# Proiect_TSC_2025.net
KiCad netlist of a schematic drawn in EAGLE
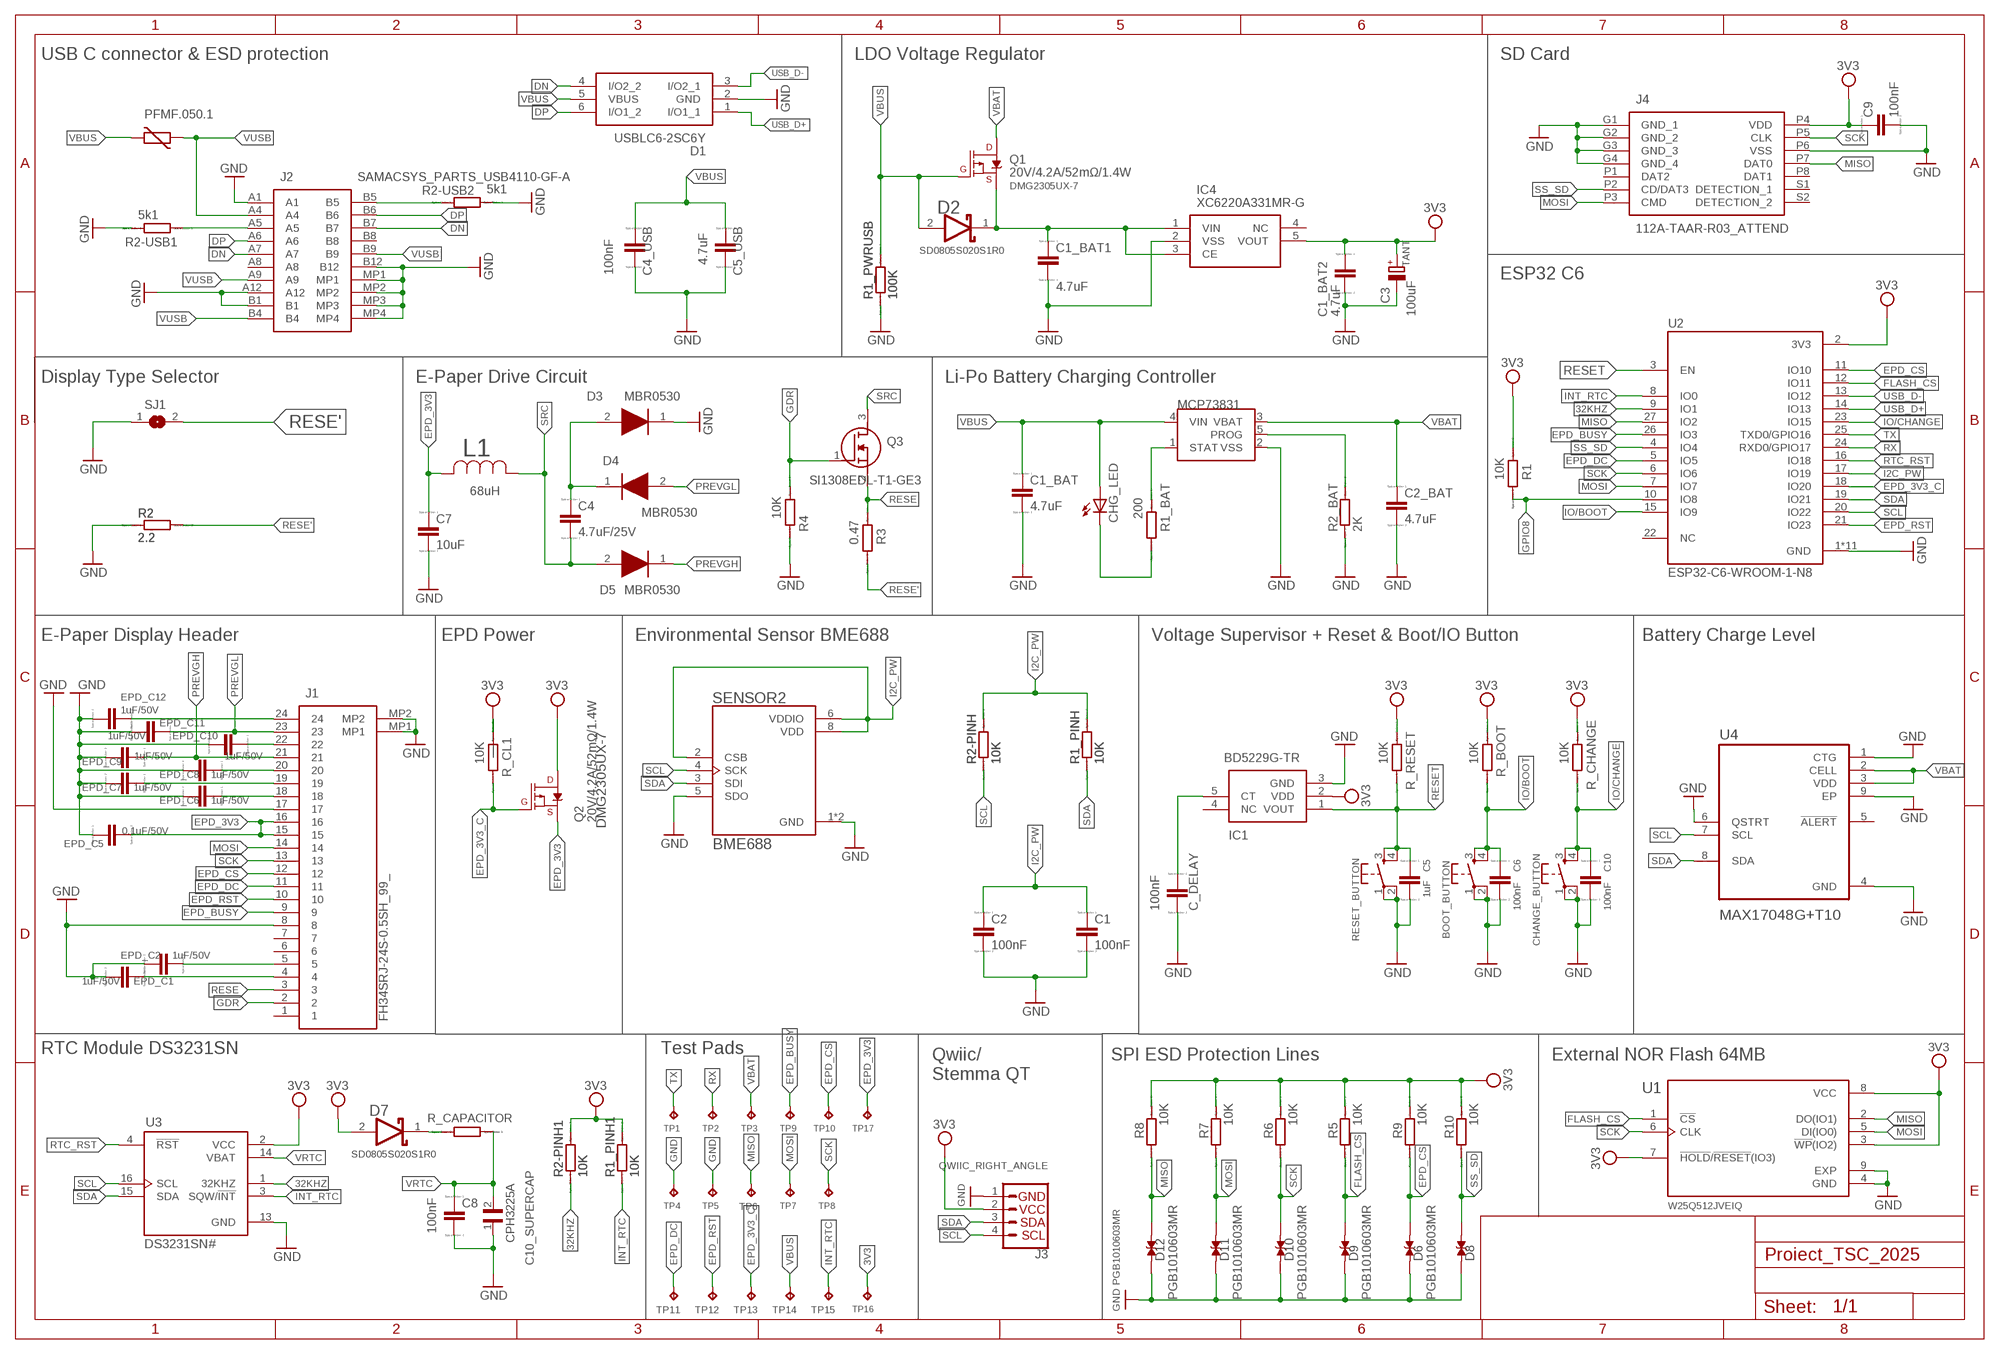
[diagram p0: schematic, sheet 1]

(export (version "E")
  (design (tool "Eeschema 10.0.6"))
  (components
    (comp (ref "BOOT_BUTTON")
      (value "BUTTON_CUSYOMV1")
      (footprint "eagle-import:MYBUTTON")
      (libsource (lib "eagle-import") (part "BUTTON_CUSYOMV1"))
    )
    (comp (ref "C1")
      (value "100nF")
      (footprint "eagle-import:ESP32_WROVER_EAGLE-LTSPICE_C0402")
      (libsource (lib "eagle-import") (part "ESP32_WROVER_EAGLE-LTSPICE_CC0402"))
    )
    (comp (ref "C1_BAT")
      (value "4.7uF")
      (footprint "eagle-import:ESP32_WROVER_EAGLE-LTSPICE_C0402")
      (libsource (lib "eagle-import") (part "ESP32_WROVER_EAGLE-LTSPICE_CC0402"))
    )
    (comp (ref "C1_BAT1")
      (value "4.7uF")
      (footprint "eagle-import:ESP32_WROVER_EAGLE-LTSPICE_C0402")
      (libsource (lib "eagle-import") (part "ESP32_WROVER_EAGLE-LTSPICE_CC0402"))
    )
    (comp (ref "C1_BAT2")
      (value "4.7uF")
      (footprint "eagle-import:ESP32_WROVER_EAGLE-LTSPICE_C0402")
      (libsource (lib "eagle-import") (part "ESP32_WROVER_EAGLE-LTSPICE_CC0402"))
    )
    (comp (ref "C2")
      (value "100nF")
      (footprint "eagle-import:ESP32_WROVER_EAGLE-LTSPICE_C0402")
      (libsource (lib "eagle-import") (part "ESP32_WROVER_EAGLE-LTSPICE_CC0402"))
    )
    (comp (ref "C2_BAT")
      (value "4.7uF")
      (footprint "eagle-import:ESP32_WROVER_EAGLE-LTSPICE_C0402")
      (libsource (lib "eagle-import") (part "ESP32_WROVER_EAGLE-LTSPICE_CC0402"))
    )
    (comp (ref "C3")
      (value "100uF")
      (footprint "eagle-import:RCL_CT3528")
      (libsource (lib "eagle-import") (part "RCL_CPOL-EUCT3528"))
    )
    (comp (ref "C4")
      (value "4.7uF/25V")
      (footprint "eagle-import:ESP32_WROVER_EAGLE-LTSPICE_C0402")
      (libsource (lib "eagle-import") (part "ESP32_WROVER_EAGLE-LTSPICE_CC0402"))
    )
    (comp (ref "C4_USB")
      (value "100nF")
      (footprint "eagle-import:EAGLE-LTSPICE_C0402")
      (libsource (lib "eagle-import") (part "EAGLE-LTSPICE_CC0402"))
    )
    (comp (ref "C5")
      (value "1uF")
      (footprint "eagle-import:ESP32_WROVER_EAGLE-LTSPICE_C0402")
      (libsource (lib "eagle-import") (part "ESP32_WROVER_EAGLE-LTSPICE_CC0402"))
    )
    (comp (ref "C5_USB")
      (value "4.7uF")
      (footprint "eagle-import:EAGLE-LTSPICE_C0402")
      (libsource (lib "eagle-import") (part "EAGLE-LTSPICE_CC0402"))
    )
    (comp (ref "C6")
      (value "100nF")
      (footprint "eagle-import:ESP32_WROVER_EAGLE-LTSPICE_C0402")
      (libsource (lib "eagle-import") (part "ESP32_WROVER_EAGLE-LTSPICE_CC0402"))
    )
    (comp (ref "C7")
      (value "10uF")
      (footprint "eagle-import:ESP32_WROVER_EAGLE-LTSPICE_C0402")
      (libsource (lib "eagle-import") (part "ESP32_WROVER_EAGLE-LTSPICE_CC0402"))
    )
    (comp (ref "C8")
      (value "100nF")
      (footprint "eagle-import:ESP32_WROVER_EAGLE-LTSPICE_C0402")
      (libsource (lib "eagle-import") (part "ESP32_WROVER_EAGLE-LTSPICE_CC0402"))
    )
    (comp (ref "C9")
      (value "100nF")
      (footprint "eagle-import:ESP32_WROVER_EAGLE-LTSPICE_C0402")
      (libsource (lib "eagle-import") (part "ESP32_WROVER_EAGLE-LTSPICE_CC0402"))
    )
    (comp (ref "C10")
      (value "100nF")
      (footprint "eagle-import:ESP32_WROVER_EAGLE-LTSPICE_C0402")
      (libsource (lib "eagle-import") (part "ESP32_WROVER_EAGLE-LTSPICE_CC0402"))
    )
    (comp (ref "C10_SUPERCAP")
      (value "CPH3225A")
      (footprint "eagle-import:CAPCP3225X100N")
      (fields (field (name "MF") "Seiko Instruments"))
      (libsource (lib "eagle-import") (part "CPH3225A"))
    )
    (comp (ref "CHANGE_BUTTON")
      (value "CHANGE_BUTTON")
      (footprint "eagle-import:MYBUTTON")
      (libsource (lib "eagle-import") (part "BUTTON_CUSYOMV1"))
    )
    (comp (ref "CHG_LED")
      (value "ADAFRUIT_LEDCHIP-LED0603")
      (footprint "eagle-import:ADAFRUIT_CHIP-LED0603")
      (libsource (lib "eagle-import") (part "ADAFRUIT_LEDCHIP-LED0603"))
    )
    (comp (ref "C_DELAY")
      (value "100nF")
      (footprint "eagle-import:ESP32_WROVER_EAGLE-LTSPICE_C0402")
      (libsource (lib "eagle-import") (part "ESP32_WROVER_EAGLE-LTSPICE_CC0402"))
    )
    (comp (ref "D1")
      (value "USBLC6-2SC6Y")
      (footprint "eagle-import:SOT95P280X145-6N")
      (fields (field (name "MF") "STMicroelectronics"))
      (libsource (lib "eagle-import") (part "USBLC6-2SC6Y"))
    )
    (comp (ref "D2")
      (value "ESP32_WROVER_AVX---SD0805S020S1R0_AVX_SD0805S020S1R0_0_0AVX_SD0805S020S1R0_0_0")
      (footprint "eagle-import:ESP32_WROVER_AVX---SD0805S020S1R0_AVX_SD0805S020S1R0_0")
      (fields
        (field (name "DIGIKEY_PART_NUMBER") "478-7800-1-ND")
        (field (name "MF") "AVX")
        (field (name "MOUSER_PART_NUMBER") "581-SD0805S020S1R0")
      )
      (libsource (lib "eagle-import") (part "ESP32_WROVER_AVX---SD0805S020S1R0_AVX_SD0805S020S1R0_0_0AVX_SD0805S020S1R0_0_0"))
    )
    (comp (ref "D3")
      (value "MBR0530")
      (footprint "eagle-import:SOD3716X135N")
      (fields (field (name "MF") "ON Semiconductor"))
      (libsource (lib "eagle-import") (part "MBR0530"))
    )
    (comp (ref "D4")
      (value "MBR0530")
      (footprint "eagle-import:SOD3716X135N")
      (fields (field (name "MF") "ON Semiconductor"))
      (libsource (lib "eagle-import") (part "MBR0530"))
    )
    (comp (ref "D5")
      (value "MBR0530")
      (footprint "eagle-import:SOD3716X135N")
      (fields (field (name "MF") "ON Semiconductor"))
      (libsource (lib "eagle-import") (part "MBR0530"))
    )
    (comp (ref "D6")
      (value "PGB1010603MR")
      (footprint "eagle-import:DIOC1608X36N")
      (fields (field (name "MF") "Littelfuse Inc."))
      (libsource (lib "eagle-import") (part "PGB1010603MR"))
    )
    (comp (ref "D7")
      (value "SD0805S020S1R0")
      (footprint "eagle-import:ESP32_WROVER_AVX---SD0805S020S1R0_AVX_SD0805S020S1R0_0")
      (fields
        (field (name "DIGIKEY_PART_NUMBER") "478-7800-1-ND")
        (field (name "MF") "AVX")
        (field (name "MOUSER_PART_NUMBER") "581-SD0805S020S1R0")
      )
      (libsource (lib "eagle-import") (part "ESP32_WROVER_AVX---SD0805S020S1R0_AVX_SD0805S020S1R0_0_0AVX_SD0805S020S1R0_0_0"))
    )
    (comp (ref "D8")
      (value "PGB1010603MR")
      (footprint "eagle-import:DIOC1608X36N")
      (fields (field (name "MF") "Littelfuse Inc."))
      (libsource (lib "eagle-import") (part "PGB1010603MR"))
    )
    (comp (ref "D9")
      (value "PGB1010603MR")
      (footprint "eagle-import:DIOC1608X36N")
      (fields (field (name "MF") "Littelfuse Inc."))
      (libsource (lib "eagle-import") (part "PGB1010603MR"))
    )
    (comp (ref "D10")
      (value "PGB1010603MR")
      (footprint "eagle-import:DIOC1608X36N")
      (fields (field (name "MF") "Littelfuse Inc."))
      (libsource (lib "eagle-import") (part "PGB1010603MR"))
    )
    (comp (ref "D11")
      (value "PGB1010603MR")
      (footprint "eagle-import:DIOC1608X36N")
      (fields (field (name "MF") "Littelfuse Inc."))
      (libsource (lib "eagle-import") (part "PGB1010603MR"))
    )
    (comp (ref "D12")
      (value "PGB1010603MR")
      (footprint "eagle-import:DIOC1608X36N")
      (fields (field (name "MF") "Littelfuse Inc."))
      (libsource (lib "eagle-import") (part "PGB1010603MR"))
    )
    (comp (ref "EPD_C1")
      (value "1uF/50V")
      (footprint "eagle-import:ESP32_WROVER_EAGLE-LTSPICE_C0402")
      (libsource (lib "eagle-import") (part "ESP32_WROVER_EAGLE-LTSPICE_CC0402"))
    )
    (comp (ref "EPD_C2")
      (value "1uF/50V")
      (footprint "eagle-import:ESP32_WROVER_EAGLE-LTSPICE_C0402")
      (libsource (lib "eagle-import") (part "ESP32_WROVER_EAGLE-LTSPICE_CC0402"))
    )
    (comp (ref "EPD_C5")
      (value "0.1uF/50V")
      (footprint "eagle-import:ESP32_WROVER_EAGLE-LTSPICE_C0402")
      (libsource (lib "eagle-import") (part "ESP32_WROVER_EAGLE-LTSPICE_CC0402"))
    )
    (comp (ref "EPD_C6")
      (value "1uF/50V")
      (footprint "eagle-import:ESP32_WROVER_EAGLE-LTSPICE_C0402")
      (libsource (lib "eagle-import") (part "ESP32_WROVER_EAGLE-LTSPICE_CC0402"))
    )
    (comp (ref "EPD_C7")
      (value "1uF/50V")
      (footprint "eagle-import:ESP32_WROVER_EAGLE-LTSPICE_C0402")
      (libsource (lib "eagle-import") (part "ESP32_WROVER_EAGLE-LTSPICE_CC0402"))
    )
    (comp (ref "EPD_C8")
      (value "1uF/50V")
      (footprint "eagle-import:ESP32_WROVER_EAGLE-LTSPICE_C0402")
      (libsource (lib "eagle-import") (part "ESP32_WROVER_EAGLE-LTSPICE_CC0402"))
    )
    (comp (ref "EPD_C9")
      (value "1uF/50V")
      (footprint "eagle-import:ESP32_WROVER_EAGLE-LTSPICE_C0402")
      (libsource (lib "eagle-import") (part "ESP32_WROVER_EAGLE-LTSPICE_CC0402"))
    )
    (comp (ref "EPD_C10")
      (value "1uF/50V")
      (footprint "eagle-import:ESP32_WROVER_EAGLE-LTSPICE_C0402")
      (libsource (lib "eagle-import") (part "ESP32_WROVER_EAGLE-LTSPICE_CC0402"))
    )
    (comp (ref "EPD_C11")
      (value "1uF/50V")
      (footprint "eagle-import:ESP32_WROVER_EAGLE-LTSPICE_C0402")
      (libsource (lib "eagle-import") (part "ESP32_WROVER_EAGLE-LTSPICE_CC0402"))
    )
    (comp (ref "EPD_C12")
      (value "1uF/50V")
      (footprint "eagle-import:ESP32_WROVER_EAGLE-LTSPICE_C0402")
      (libsource (lib "eagle-import") (part "ESP32_WROVER_EAGLE-LTSPICE_CC0402"))
    )
    (comp (ref "IC1")
      (value "BD5229G-TR")
      (footprint "eagle-import:SOT95P280X125-5N")
      (fields (field (name "MOUSER_PART_NUMBER") "755-BD5229G-TR"))
      (libsource (lib "eagle-import") (part "BD5229G-TR"))
    )
    (comp (ref "IC4")
      (value "XC6220A331MR-G")
      (footprint "eagle-import:SOT95P280X120-5N")
      (fields (field (name "MOUSER_PART_NUMBER") "865-XC6220A331MR-G"))
      (libsource (lib "eagle-import") (part "XC6220A331MR-G"))
    )
    (comp (ref "J1")
      (value "FH34SRJ-24S-0.5SH_99_")
      (footprint "eagle-import:FH34SRJ24S05SH99")
      (fields
        (field (name "MANUFACTURER_PART_NUMBER") "FH34SRJ-24S-0.5SH(99)")
        (field (name "MOUSER_PART_NUMBER") "798-FH34SRJ24S05SH99")
      )
      (libsource (lib "eagle-import") (part "FH34SRJ-24S-0.5SH_99_"))
    )
    (comp (ref "J2")
      (value "SAMACSYS_PARTS_USB4110-GF-A")
      (footprint "eagle-import:SAMACSYS_PARTS_USB4110GFA")
      (fields
        (field (name "MANUFACTURER_PART_NUMBER") "USB4110-GF-A")
        (field (name "MOUSER_PART_NUMBER") "640-USB4110-GF-A")
      )
      (libsource (lib "eagle-import") (part "SAMACSYS_PARTS_USB4110-GF-A"))
    )
    (comp (ref "J3")
      (value "QWIIC_RIGHT_ANGLE")
      (footprint "eagle-import:JST04_1MM_RA")
      (libsource (lib "eagle-import") (part "QWIIC_CONNECTORJS-1MM"))
    )
    (comp (ref "J4")
      (value "112A-TAAR-R03_ATTEND")
      (footprint "eagle-import:112ATAARR03ATTEND")
      (fields (field (name "MANUFACTURER_PART_NUMBER") "112A-TAAR-R03 ATTEND"))
      (libsource (lib "eagle-import") (part "112A-TAAR-R03_ATTEND"))
    )
    (comp (ref "L1")
      (value "68uH")
      (footprint "eagle-import:IND_4828-WE-TPC_WRE")
      (fields
        (field (name "MANUFACTURER_PART_NUMBER") "744043680")
        (field (name "COPYRIGHT") "Copyright (C) 2024 Ultra Librarian. All rights reserved.")
      )
      (libsource (lib "eagle-import") (part "744043680IND_4828-WE-TPC_WRE"))
    )
    (comp (ref "MCP73831")
      (value "MCP73831")
      (footprint "eagle-import:ESP32_WROVER_SPARKFUN-IC-POWER_SOT23-5")
      (libsource (lib "eagle-import") (part "ESP32_WROVER_SPARKFUN-IC-POWER_MCP73831"))
    )
    (comp (ref "PFMF.050.1")
      (value "ESP32C6_VARISTORCN1812")
      (footprint "eagle-import:ESP32C6_VARISTOR_CT_CN1812")
      (libsource (lib "eagle-import") (part "ESP32C6_VARISTORCN1812"))
    )
    (comp (ref "Q1")
      (value "20V/4.2A/52mΩ/1.4W")
      (footprint "eagle-import:ESP32_WROVER_SPARKFUN-DISCRETESEMI_SOT23-3")
      (libsource (lib "eagle-import") (part "ESP32_WROVER_SPARKFUN-DISCRETESEMI_MOSFET_PCH-DMG2305UX-7"))
    )
    (comp (ref "Q2")
      (value "20V/4.2A/52mΩ/1.4W")
      (footprint "eagle-import:ESP32_WROVER_SPARKFUN-DISCRETESEMI_SOT23-3")
      (libsource (lib "eagle-import") (part "ESP32_WROVER_SPARKFUN-DISCRETESEMI_MOSFET_PCH-DMG2305UX-7"))
    )
    (comp (ref "Q3")
      (value "SI1308EDL-T1-GE3")
      (footprint "eagle-import:SOT65P210X110-3N")
      (fields (field (name "MF") "Vishay Siliconix"))
      (libsource (lib "eagle-import") (part "SI1308EDL-T1-GE3"))
    )
    (comp (ref "R1")
      (value "10K")
      (footprint "eagle-import:ESP32_WROVER_EAGLE-LTSPICE_R0402")
      (libsource (lib "eagle-import") (part "ESP32_WROVER_EAGLE-LTSPICE_RR0402"))
    )
    (comp (ref "R1_BAT")
      (value "200")
      (footprint "eagle-import:ESP32_WROVER_EAGLE-LTSPICE_R0402")
      (libsource (lib "eagle-import") (part "ESP32_WROVER_EAGLE-LTSPICE_RR0402"))
    )
    (comp (ref "R1_PINH")
      (value "10K")
      (footprint "eagle-import:ESP32_WROVER_EAGLE-LTSPICE_R0402")
      (libsource (lib "eagle-import") (part "ESP32_WROVER_EAGLE-LTSPICE_RR0402"))
    )
    (comp (ref "R1_PINH1")
      (value "10K")
      (footprint "eagle-import:ESP32_WROVER_EAGLE-LTSPICE_R0402")
      (libsource (lib "eagle-import") (part "ESP32_WROVER_EAGLE-LTSPICE_RR0402"))
    )
    (comp (ref "R1_PWRUSB")
      (value "100K")
      (footprint "eagle-import:ESP32_WROVER_EAGLE-LTSPICE_R0402")
      (libsource (lib "eagle-import") (part "ESP32_WROVER_EAGLE-LTSPICE_RR0402"))
    )
    (comp (ref "R2")
      (value "2.2")
      (footprint "eagle-import:ESP32_WROVER_EAGLE-LTSPICE_R0402")
      (libsource (lib "eagle-import") (part "ESP32_WROVER_EAGLE-LTSPICE_RR0402"))
    )
    (comp (ref "R2-PINH")
      (value "10K")
      (footprint "eagle-import:ESP32_WROVER_EAGLE-LTSPICE_R0402")
      (libsource (lib "eagle-import") (part "ESP32_WROVER_EAGLE-LTSPICE_RR0402"))
    )
    (comp (ref "R2-PINH1")
      (value "10K")
      (footprint "eagle-import:ESP32_WROVER_EAGLE-LTSPICE_R0402")
      (libsource (lib "eagle-import") (part "ESP32_WROVER_EAGLE-LTSPICE_RR0402"))
    )
    (comp (ref "R2-USB1")
      (value "5k1")
      (footprint "eagle-import:ESP32_WROVER_EAGLE-LTSPICE_R0402")
      (libsource (lib "eagle-import") (part "ESP32_WROVER_EAGLE-LTSPICE_RR0402"))
    )
    (comp (ref "R2-USB2")
      (value "5k1")
      (footprint "eagle-import:ESP32_WROVER_EAGLE-LTSPICE_R0402")
      (libsource (lib "eagle-import") (part "ESP32_WROVER_EAGLE-LTSPICE_RR0402"))
    )
    (comp (ref "R2_BAT")
      (value "2K")
      (footprint "eagle-import:ESP32_WROVER_EAGLE-LTSPICE_R0402")
      (libsource (lib "eagle-import") (part "ESP32_WROVER_EAGLE-LTSPICE_RR0402"))
    )
    (comp (ref "R3")
      (value "0.47")
      (footprint "eagle-import:ESP32_WROVER_EAGLE-LTSPICE_R0402")
      (libsource (lib "eagle-import") (part "ESP32_WROVER_EAGLE-LTSPICE_RR0402"))
    )
    (comp (ref "R4")
      (value "10K")
      (footprint "eagle-import:ESP32_WROVER_EAGLE-LTSPICE_R0402")
      (libsource (lib "eagle-import") (part "ESP32_WROVER_EAGLE-LTSPICE_RR0402"))
    )
    (comp (ref "R5")
      (value "10K")
      (footprint "eagle-import:ESP32_WROVER_EAGLE-LTSPICE_R0402")
      (libsource (lib "eagle-import") (part "ESP32_WROVER_EAGLE-LTSPICE_RR0402"))
    )
    (comp (ref "R6")
      (value "10K")
      (footprint "eagle-import:ESP32_WROVER_EAGLE-LTSPICE_R0402")
      (libsource (lib "eagle-import") (part "ESP32_WROVER_EAGLE-LTSPICE_RR0402"))
    )
    (comp (ref "R7")
      (value "10K")
      (footprint "eagle-import:ESP32_WROVER_EAGLE-LTSPICE_R0402")
      (libsource (lib "eagle-import") (part "ESP32_WROVER_EAGLE-LTSPICE_RR0402"))
    )
    (comp (ref "R8")
      (value "10K")
      (footprint "eagle-import:ESP32_WROVER_EAGLE-LTSPICE_R0402")
      (libsource (lib "eagle-import") (part "ESP32_WROVER_EAGLE-LTSPICE_RR0402"))
    )
    (comp (ref "R9")
      (value "10K")
      (footprint "eagle-import:ESP32_WROVER_EAGLE-LTSPICE_R0402")
      (libsource (lib "eagle-import") (part "ESP32_WROVER_EAGLE-LTSPICE_RR0402"))
    )
    (comp (ref "R10")
      (value "10K")
      (footprint "eagle-import:ESP32_WROVER_EAGLE-LTSPICE_R0402")
      (libsource (lib "eagle-import") (part "ESP32_WROVER_EAGLE-LTSPICE_RR0402"))
    )
    (comp (ref "RESET_BUTTON")
      (value "BUTTON_CUSYOMV1")
      (footprint "eagle-import:MYBUTTON")
      (libsource (lib "eagle-import") (part "BUTTON_CUSYOMV1"))
    )
    (comp (ref "R_BOOT")
      (value "10K")
      (footprint "eagle-import:ESP32_WROVER_EAGLE-LTSPICE_R0402")
      (libsource (lib "eagle-import") (part "ESP32_WROVER_EAGLE-LTSPICE_RR0402"))
    )
    (comp (ref "R_CAPACITOR")
      (value "ESP32_WROVER_EAGLE-LTSPICE_RR0402")
      (footprint "eagle-import:ESP32_WROVER_EAGLE-LTSPICE_R0402")
      (libsource (lib "eagle-import") (part "ESP32_WROVER_EAGLE-LTSPICE_RR0402"))
    )
    (comp (ref "R_CHANGE")
      (value "10K")
      (footprint "eagle-import:ESP32_WROVER_EAGLE-LTSPICE_R0402")
      (libsource (lib "eagle-import") (part "ESP32_WROVER_EAGLE-LTSPICE_RR0402"))
    )
    (comp (ref "R_CL1")
      (value "10K")
      (footprint "eagle-import:ESP32_WROVER_EAGLE-LTSPICE_R0402")
      (libsource (lib "eagle-import") (part "ESP32_WROVER_EAGLE-LTSPICE_RR0402"))
    )
    (comp (ref "R_RESET")
      (value "10K")
      (footprint "eagle-import:ESP32_WROVER_EAGLE-LTSPICE_R0402")
      (libsource (lib "eagle-import") (part "ESP32_WROVER_EAGLE-LTSPICE_RR0402"))
    )
    (comp (ref "SENSOR2")
      (value "BME688")
      (footprint "eagle-import:ESP32_WROVER_BME680_PSON80P300X300X100-8N")
      (fields (field (name "MF") "Bosch Sensortec") (field (name "MP") "BME680"))
      (libsource (lib "eagle-import") (part "ESP32_WROVER_BME680_BME680"))
    )
    (comp (ref "SJ1") (value "0") (footprint "eagle-import:SJ") (libsource (lib "eagle-import") (part "SJ")))
    (comp (ref "TP1")
      (value "TPTP20R")
      (footprint "eagle-import:TP20R")
      (libsource (lib "eagle-import") (part "TPTP20R"))
    )
    (comp (ref "TP2")
      (value "TPTP20R")
      (footprint "eagle-import:TP20R")
      (libsource (lib "eagle-import") (part "TPTP20R"))
    )
    (comp (ref "TP3")
      (value "TPTP20R")
      (footprint "eagle-import:TP20R")
      (libsource (lib "eagle-import") (part "TPTP20R"))
    )
    (comp (ref "TP4")
      (value "TPTP20R")
      (footprint "eagle-import:TP20R")
      (libsource (lib "eagle-import") (part "TPTP20R"))
    )
    (comp (ref "TP5")
      (value "TPTP20R")
      (footprint "eagle-import:TP20R")
      (libsource (lib "eagle-import") (part "TPTP20R"))
    )
    (comp (ref "TP6")
      (value "TPTP20R")
      (footprint "eagle-import:TP20R")
      (libsource (lib "eagle-import") (part "TPTP20R"))
    )
    (comp (ref "TP7")
      (value "TPTP20R")
      (footprint "eagle-import:TP20R")
      (libsource (lib "eagle-import") (part "TPTP20R"))
    )
    (comp (ref "TP8")
      (value "TPTP20R")
      (footprint "eagle-import:TP20R")
      (libsource (lib "eagle-import") (part "TPTP20R"))
    )
    (comp (ref "TP9")
      (value "TPTP20R")
      (footprint "eagle-import:TP20R")
      (libsource (lib "eagle-import") (part "TPTP20R"))
    )
    (comp (ref "TP10")
      (value "TPTP20R")
      (footprint "eagle-import:TP20R")
      (libsource (lib "eagle-import") (part "TPTP20R"))
    )
    (comp (ref "TP11")
      (value "TPTP20R")
      (footprint "eagle-import:TP20R")
      (libsource (lib "eagle-import") (part "TPTP20R"))
    )
    (comp (ref "TP12")
      (value "TPTP20R")
      (footprint "eagle-import:TP20R")
      (libsource (lib "eagle-import") (part "TPTP20R"))
    )
    (comp (ref "TP13")
      (value "TPTP20R")
      (footprint "eagle-import:TP20R")
      (libsource (lib "eagle-import") (part "TPTP20R"))
    )
    (comp (ref "TP14")
      (value "TPTP20R")
      (footprint "eagle-import:TP20R")
      (libsource (lib "eagle-import") (part "TPTP20R"))
    )
    (comp (ref "TP15")
      (value "TPTP20R")
      (footprint "eagle-import:TP20R")
      (libsource (lib "eagle-import") (part "TPTP20R"))
    )
    (comp (ref "TP16")
      (value "TPTP20R")
      (footprint "eagle-import:TP20R")
      (libsource (lib "eagle-import") (part "TPTP20R"))
    )
    (comp (ref "TP17")
      (value "TPTP20R")
      (footprint "eagle-import:TP20R")
      (libsource (lib "eagle-import") (part "TPTP20R"))
    )
    (comp (ref "U1")
      (value "W25Q512JVEIQ")
      (footprint "eagle-import:SON127P600X800X80-9N")
      (fields (field (name "MF") "Winbond Electronics"))
      (libsource (lib "eagle-import") (part "W25Q512JVEIQ"))
    )
    (comp (ref "U2")
      (value "ESP32-C6-WROOM-1-N8")
      (footprint "eagle-import:XCVR_ESP32-C6-WROOM-1-N8")
      (fields (field (name "MF") "Espressif Systems"))
      (libsource (lib "eagle-import") (part "ESP32-C6-WROOM-1-N8"))
    )
    (comp (ref "U3")
      (value "DS3231SN#")
      (footprint "eagle-import:SOIC127P1032X265-16N")
      (fields (field (name "MF") "Analog Devices"))
      (libsource (lib "eagle-import") (part "DS3231SN#"))
    )
    (comp (ref "U4")
      (value "MAX17048G+T10")
      (footprint "eagle-import:SON50P200X200X80-9N")
      (fields (field (name "MF") "Analog Devices"))
      (libsource (lib "eagle-import") (part "MAX17048G+T10"))
    )
  )
  (nets
    (net (code "1") (name "3V3") (class "Default")
      (node (ref "C1_BAT2") (pin "1") (pinfunction "1_1") (pintype "passive"))
      (node (ref "C3") (pin "+") (pinfunction "+_+") (pintype "passive"))
      (node (ref "C9") (pin "1") (pinfunction "1_1") (pintype "passive"))
      (node (ref "D7") (pin "2") (pinfunction "ANODE_2") (pintype "bidirectional"))
      (node (ref "IC1") (pin "2") (pinfunction "VDD_2") (pintype "bidirectional"))
      (node (ref "IC4") (pin "5") (pinfunction "VOUT_5") (pintype "bidirectional"))
      (node (ref "J3") (pin "2") (pinfunction "2_2") (pintype "power_in"))
      (node (ref "J4") (pin "P4") (pinfunction "VDD_P4") (pintype "bidirectional"))
      (node (ref "Q2") (pin "3") (pinfunction "D_3") (pintype "bidirectional"))
      (node (ref "R1") (pin "2") (pinfunction "2_2") (pintype "passive"))
      (node (ref "R10") (pin "2") (pinfunction "2_2") (pintype "passive"))
      (node (ref "R1_PINH1") (pin "2") (pinfunction "2_2") (pintype "passive"))
      (node (ref "R2-PINH1") (pin "2") (pinfunction "2_2") (pintype "passive"))
      (node (ref "R5") (pin "2") (pinfunction "2_2") (pintype "passive"))
      (node (ref "R6") (pin "2") (pinfunction "2_2") (pintype "passive"))
      (node (ref "R7") (pin "2") (pinfunction "2_2") (pintype "passive"))
      (node (ref "R8") (pin "2") (pinfunction "2_2") (pintype "passive"))
      (node (ref "R9") (pin "2") (pinfunction "2_2") (pintype "passive"))
      (node (ref "R_BOOT") (pin "2") (pinfunction "2_2") (pintype "passive"))
      (node (ref "R_CHANGE") (pin "2") (pinfunction "2_2") (pintype "passive"))
      (node (ref "R_CL1") (pin "2") (pinfunction "2_2") (pintype "passive"))
      (node (ref "R_RESET") (pin "2") (pinfunction "2_2") (pintype "passive"))
      (node (ref "TP16") (pin "TP") (pinfunction "TP_TP") (pintype "input"))
      (node (ref "U1") (pin "3") (pinfunction "~{WP}(IO2)_3") (pintype "bidirectional"))
      (node (ref "U1") (pin "7") (pinfunction "~{HOLD}/~{RESET}(IO3)_7") (pintype "bidirectional"))
      (node (ref "U1") (pin "8") (pinfunction "VCC_8") (pintype "power_in"))
      (node (ref "U2") (pin "2") (pinfunction "3V3_2") (pintype "power_in"))
      (node (ref "U3") (pin "2") (pinfunction "VCC_2") (pintype "power_in"))
    )
    (net (code "2") (name "32KHZ") (class "Default")
      (node (ref "R2-PINH1") (pin "1") (pinfunction "1_1") (pintype "passive"))
      (node (ref "U2") (pin "9") (pinfunction "IO1_9") (pintype "bidirectional"))
      (node (ref "U3") (pin "1") (pinfunction "32KHZ_1") (pintype "output"))
    )
    (net (code "3") (name "DN") (class "Default")
      (node (ref "D1") (pin "4") (pinfunction "I/O2_2_4") (pintype "bidirectional"))
      (node (ref "J2") (pin "A7") (pinfunction "A7_A7") (pintype "bidirectional"))
      (node (ref "J2") (pin "B7") (pinfunction "B7_B7") (pintype "bidirectional"))
    )
    (net (code "4") (name "DP") (class "Default")
      (node (ref "D1") (pin "6") (pinfunction "I/O1_2_6") (pintype "bidirectional"))
      (node (ref "J2") (pin "A6") (pinfunction "A6_A6") (pintype "bidirectional"))
      (node (ref "J2") (pin "B6") (pinfunction "B6_B6") (pintype "bidirectional"))
    )
    (net (code "5") (name "EPD_3V3") (class "Default")
      (node (ref "C7") (pin "1") (pinfunction "1_1") (pintype "passive"))
      (node (ref "EPD_C5") (pin "2") (pinfunction "2_2") (pintype "passive"))
      (node (ref "J1") (pin "15") (pinfunction "15_15") (pintype "bidirectional"))
      (node (ref "J1") (pin "16") (pinfunction "16_16") (pintype "bidirectional"))
      (node (ref "L1") (pin "2") (pinfunction "2_2") (pintype "passive"))
      (node (ref "Q2") (pin "2") (pinfunction "S_2") (pintype "bidirectional"))
      (node (ref "TP17") (pin "TP") (pinfunction "TP_TP") (pintype "input"))
    )
    (net (code "6") (name "EPD_3V3_C") (class "Default")
      (node (ref "Q2") (pin "1") (pinfunction "G_1") (pintype "bidirectional"))
      (node (ref "R_CL1") (pin "1") (pinfunction "1_1") (pintype "passive"))
      (node (ref "TP13") (pin "TP") (pinfunction "TP_TP") (pintype "input"))
      (node (ref "U2") (pin "18") (pinfunction "IO20_18") (pintype "bidirectional"))
    )
    (net (code "7") (name "EPD_BUSY") (class "Default")
      (node (ref "J1") (pin "9") (pinfunction "9_9") (pintype "bidirectional"))
      (node (ref "TP9") (pin "TP") (pinfunction "TP_TP") (pintype "input"))
      (node (ref "U2") (pin "26") (pinfunction "IO3_26") (pintype "bidirectional"))
    )
    (net (code "8") (name "EPD_CS") (class "Default")
      (node (ref "D6") (pin "2") (pinfunction "2_2") (pintype "passive"))
      (node (ref "J1") (pin "12") (pinfunction "12_12") (pintype "bidirectional"))
      (node (ref "R9") (pin "1") (pinfunction "1_1") (pintype "passive"))
      (node (ref "TP10") (pin "TP") (pinfunction "TP_TP") (pintype "input"))
      (node (ref "U2") (pin "11") (pinfunction "IO10_11") (pintype "bidirectional"))
    )
    (net (code "9") (name "EPD_DC") (class "Default")
      (node (ref "J1") (pin "11") (pinfunction "11_11") (pintype "bidirectional"))
      (node (ref "TP11") (pin "TP") (pinfunction "TP_TP") (pintype "input"))
      (node (ref "U2") (pin "5") (pinfunction "IO5_5") (pintype "bidirectional"))
    )
    (net (code "10") (name "EPD_RST") (class "Default")
      (node (ref "J1") (pin "10") (pinfunction "10_10") (pintype "bidirectional"))
      (node (ref "TP12") (pin "TP") (pinfunction "TP_TP") (pintype "input"))
      (node (ref "U2") (pin "21") (pinfunction "IO23_21") (pintype "bidirectional"))
    )
    (net (code "11") (name "FLASH_CS") (class "Default")
      (node (ref "D9") (pin "2") (pinfunction "2_2") (pintype "passive"))
      (node (ref "R5") (pin "1") (pinfunction "1_1") (pintype "passive"))
      (node (ref "U1") (pin "1") (pinfunction "~{CS}_1") (pintype "input"))
      (node (ref "U2") (pin "12") (pinfunction "IO11_12") (pintype "bidirectional"))
    )
    (net (code "12") (name "GDR") (class "Default")
      (node (ref "J1") (pin "2") (pinfunction "2_2") (pintype "bidirectional"))
      (node (ref "Q3") (pin "1") (pinfunction "G_1") (pintype "bidirectional"))
      (node (ref "R4") (pin "2") (pinfunction "2_2") (pintype "passive"))
    )
    (net (code "13") (name "GND") (class "Default")
      (node (ref "BOOT_BUTTON") (pin "1") (pinfunction "1_1") (pintype "passive"))
      (node (ref "BOOT_BUTTON") (pin "2") (pinfunction "2_2") (pintype "passive"))
      (node (ref "C1") (pin "2") (pinfunction "2_2") (pintype "passive"))
      (node (ref "C10") (pin "2") (pinfunction "2_2") (pintype "passive"))
      (node (ref "C10_SUPERCAP") (pin "1") (pinfunction "1_1") (pintype "passive"))
      (node (ref "C1_BAT") (pin "2") (pinfunction "2_2") (pintype "passive"))
      (node (ref "C1_BAT1") (pin "2") (pinfunction "2_2") (pintype "passive"))
      (node (ref "C1_BAT2") (pin "2") (pinfunction "2_2") (pintype "passive"))
      (node (ref "C2") (pin "2") (pinfunction "2_2") (pintype "passive"))
      (node (ref "C2_BAT") (pin "2") (pinfunction "2_2") (pintype "passive"))
      (node (ref "C3") (pin "-") (pinfunction "-_-") (pintype "passive"))
      (node (ref "C4_USB") (pin "2") (pinfunction "2_2") (pintype "passive"))
      (node (ref "C5") (pin "2") (pinfunction "2_2") (pintype "passive"))
      (node (ref "C5_USB") (pin "2") (pinfunction "2_2") (pintype "passive"))
      (node (ref "C6") (pin "2") (pinfunction "2_2") (pintype "passive"))
      (node (ref "C7") (pin "2") (pinfunction "2_2") (pintype "passive"))
      (node (ref "C8") (pin "2") (pinfunction "2_2") (pintype "passive"))
      (node (ref "C9") (pin "2") (pinfunction "2_2") (pintype "passive"))
      (node (ref "CHANGE_BUTTON") (pin "1") (pinfunction "1_1") (pintype "passive"))
      (node (ref "CHANGE_BUTTON") (pin "2") (pinfunction "2_2") (pintype "passive"))
      (node (ref "C_DELAY") (pin "2") (pinfunction "2_2") (pintype "passive"))
      (node (ref "D1") (pin "2") (pinfunction "GND_2") (pintype "bidirectional"))
      (node (ref "D10") (pin "1") (pinfunction "1_1") (pintype "passive"))
      (node (ref "D11") (pin "1") (pinfunction "1_1") (pintype "passive"))
      (node (ref "D12") (pin "1") (pinfunction "1_1") (pintype "passive"))
      (node (ref "D3") (pin "1") (pinfunction "K_1") (pintype "bidirectional"))
      (node (ref "D6") (pin "1") (pinfunction "1_1") (pintype "passive"))
      (node (ref "D8") (pin "1") (pinfunction "1_1") (pintype "passive"))
      (node (ref "D9") (pin "1") (pinfunction "1_1") (pintype "passive"))
      (node (ref "EPD_C1") (pin "2") (pinfunction "2_2") (pintype "passive"))
      (node (ref "EPD_C10") (pin "2") (pinfunction "2_2") (pintype "passive"))
      (node (ref "EPD_C11") (pin "2") (pinfunction "2_2") (pintype "passive"))
      (node (ref "EPD_C12") (pin "2") (pinfunction "2_2") (pintype "passive"))
      (node (ref "EPD_C2") (pin "2") (pinfunction "2_2") (pintype "passive"))
      (node (ref "EPD_C5") (pin "1") (pinfunction "1_1") (pintype "passive"))
      (node (ref "EPD_C6") (pin "2") (pinfunction "2_2") (pintype "passive"))
      (node (ref "EPD_C7") (pin "2") (pinfunction "2_2") (pintype "passive"))
      (node (ref "EPD_C8") (pin "2") (pinfunction "2_2") (pintype "passive"))
      (node (ref "EPD_C9") (pin "2") (pinfunction "2_2") (pintype "passive"))
      (node (ref "IC1") (pin "3") (pinfunction "GND_3") (pintype "bidirectional"))
      (node (ref "IC4") (pin "2") (pinfunction "VSS_2") (pintype "bidirectional"))
      (node (ref "J1") (pin "17") (pinfunction "17_17") (pintype "bidirectional"))
      (node (ref "J1") (pin "8") (pinfunction "8_8") (pintype "bidirectional"))
      (node (ref "J1") (pin "MP1") (pinfunction "MP1_MP1") (pintype "bidirectional"))
      (node (ref "J1") (pin "MP2") (pinfunction "MP2_MP2") (pintype "bidirectional"))
      (node (ref "J2") (pin "A1") (pinfunction "A1_A1") (pintype "bidirectional"))
      (node (ref "J2") (pin "A12") (pinfunction "A12_A12") (pintype "bidirectional"))
      (node (ref "J2") (pin "B1") (pinfunction "B1_B1") (pintype "bidirectional"))
      (node (ref "J2") (pin "B12") (pinfunction "B12_B12") (pintype "bidirectional"))
      (node (ref "J2") (pin "MP1") (pinfunction "MP1_MP1") (pintype "bidirectional"))
      (node (ref "J2") (pin "MP2") (pinfunction "MP2_MP2") (pintype "bidirectional"))
      (node (ref "J2") (pin "MP3") (pinfunction "MP3_MP3") (pintype "bidirectional"))
      (node (ref "J2") (pin "MP4") (pinfunction "MP4_MP4") (pintype "bidirectional"))
      (node (ref "J3") (pin "1") (pinfunction "1_1") (pintype "power_in"))
      (node (ref "J4") (pin "G1") (pinfunction "GND_1_G1") (pintype "bidirectional"))
      (node (ref "J4") (pin "G2") (pinfunction "GND_2_G2") (pintype "bidirectional"))
      (node (ref "J4") (pin "G3") (pinfunction "GND_3_G3") (pintype "bidirectional"))
      (node (ref "J4") (pin "G4") (pinfunction "GND_4_G4") (pintype "bidirectional"))
      (node (ref "J4") (pin "P6") (pinfunction "VSS_P6") (pintype "bidirectional"))
      (node (ref "MCP73831") (pin "2") (pinfunction "VSS_2") (pintype "power_in"))
      (node (ref "R1_PWRUSB") (pin "1") (pinfunction "1_1") (pintype "passive"))
      (node (ref "R2") (pin "1") (pinfunction "1_1") (pintype "passive"))
      (node (ref "R2-USB1") (pin "1") (pinfunction "1_1") (pintype "passive"))
      (node (ref "R2-USB2") (pin "2") (pinfunction "2_2") (pintype "passive"))
      (node (ref "R2_BAT") (pin "1") (pinfunction "1_1") (pintype "passive"))
      (node (ref "R4") (pin "1") (pinfunction "1_1") (pintype "passive"))
      (node (ref "RESET_BUTTON") (pin "1") (pinfunction "1_1") (pintype "passive"))
      (node (ref "RESET_BUTTON") (pin "2") (pinfunction "2_2") (pintype "passive"))
      (node (ref "SENSOR2") (pin "1") (pinfunction "GND_1") (pintype "power_in"))
      (node (ref "SENSOR2") (pin "5") (pinfunction "SDO_5") (pintype "bidirectional"))
      (node (ref "SENSOR2") (pin "7") (pinfunction "GND_7") (pintype "power_in"))
      (node (ref "SJ1") (pin "1") (pinfunction "1_1") (pintype "passive"))
      (node (ref "TP4") (pin "TP") (pinfunction "TP_TP") (pintype "input"))
      (node (ref "TP5") (pin "TP") (pinfunction "TP_TP") (pintype "input"))
      (node (ref "U1") (pin "4") (pinfunction "GND_4") (pintype "power_in"))
      (node (ref "U1") (pin "9") (pinfunction "EXP_9") (pintype "passive"))
      (node (ref "U2") (pin "1") (pinfunction "GND_1") (pintype "power_in"))
      (node (ref "U2") (pin "28") (pinfunction "GND_28") (pintype "power_in"))
      (node (ref "U2") (pin "29_1") (pinfunction "GND_29_1") (pintype "power_in"))
      (node (ref "U2") (pin "29_2") (pinfunction "GND_29_2") (pintype "power_in"))
      (node (ref "U2") (pin "29_3") (pinfunction "GND_29_3") (pintype "power_in"))
      (node (ref "U2") (pin "29_4") (pinfunction "GND_29_4") (pintype "power_in"))
      (node (ref "U2") (pin "29_5") (pinfunction "GND_29_5") (pintype "power_in"))
      (node (ref "U2") (pin "29_6") (pinfunction "GND_29_6") (pintype "power_in"))
      (node (ref "U2") (pin "29_7") (pinfunction "GND_29_7") (pintype "power_in"))
      (node (ref "U2") (pin "29_8") (pinfunction "GND_29_8") (pintype "power_in"))
      (node (ref "U2") (pin "29_9") (pinfunction "GND_29_9") (pintype "power_in"))
      (node (ref "U3") (pin "13") (pinfunction "GND_13") (pintype "power_in"))
      (node (ref "U4") (pin "1") (pinfunction "CTG_1") (pintype "power_in"))
      (node (ref "U4") (pin "4") (pinfunction "GND_4") (pintype "power_in"))
      (node (ref "U4") (pin "6") (pinfunction "QSTRT_6") (pintype "input"))
      (node (ref "U4") (pin "9") (pinfunction "EP_9") (pintype "power_in"))
    )
    (net (code "14") (name "GPIO8") (class "Default")
      (node (ref "R1") (pin "1") (pinfunction "1_1") (pintype "passive"))
      (node (ref "U2") (pin "10") (pinfunction "IO8_10") (pintype "bidirectional"))
    )
    (net (code "15") (name "I2C_PW") (class "Default")
      (node (ref "C1") (pin "1") (pinfunction "1_1") (pintype "passive"))
      (node (ref "C2") (pin "1") (pinfunction "1_1") (pintype "passive"))
      (node (ref "R1_PINH") (pin "2") (pinfunction "2_2") (pintype "passive"))
      (node (ref "R2-PINH") (pin "2") (pinfunction "2_2") (pintype "passive"))
      (node (ref "SENSOR2") (pin "2") (pinfunction "CSB_2") (pintype "input"))
      (node (ref "SENSOR2") (pin "6") (pinfunction "VDDIO_6") (pintype "power_in"))
      (node (ref "SENSOR2") (pin "8") (pinfunction "VDD_8") (pintype "power_in"))
      (node (ref "U2") (pin "17") (pinfunction "IO19_17") (pintype "bidirectional"))
    )
    (net (code "16") (name "INT_RTC") (class "Default")
      (node (ref "R1_PINH1") (pin "1") (pinfunction "1_1") (pintype "passive"))
      (node (ref "TP15") (pin "TP") (pinfunction "TP_TP") (pintype "input"))
      (node (ref "U2") (pin "8") (pinfunction "IO0_8") (pintype "bidirectional"))
      (node (ref "U3") (pin "3") (pinfunction "SQW/~{INT}_3") (pintype "output"))
    )
    (net (code "17") (name "IO{slash}BOOT") (class "Default")
      (node (ref "BOOT_BUTTON") (pin "3") (pinfunction "3_3") (pintype "passive"))
      (node (ref "BOOT_BUTTON") (pin "4") (pinfunction "4_4") (pintype "passive"))
      (node (ref "C6") (pin "1") (pinfunction "1_1") (pintype "passive"))
      (node (ref "R_BOOT") (pin "1") (pinfunction "1_1") (pintype "passive"))
      (node (ref "U2") (pin "15") (pinfunction "IO9_15") (pintype "bidirectional"))
    )
    (net (code "18") (name "IO{slash}CHANGE") (class "Default")
      (node (ref "C10") (pin "1") (pinfunction "1_1") (pintype "passive"))
      (node (ref "CHANGE_BUTTON") (pin "3") (pinfunction "3_3") (pintype "passive"))
      (node (ref "CHANGE_BUTTON") (pin "4") (pinfunction "4_4") (pintype "passive"))
      (node (ref "R_CHANGE") (pin "1") (pinfunction "1_1") (pintype "passive"))
      (node (ref "U2") (pin "23") (pinfunction "IO15_23") (pintype "bidirectional"))
    )
    (net (code "19") (name "MISO") (class "Default")
      (node (ref "D12") (pin "2") (pinfunction "2_2") (pintype "passive"))
      (node (ref "J4") (pin "P7") (pinfunction "DAT0_P7") (pintype "bidirectional"))
      (node (ref "R8") (pin "1") (pinfunction "1_1") (pintype "passive"))
      (node (ref "TP6") (pin "TP") (pinfunction "TP_TP") (pintype "input"))
      (node (ref "U1") (pin "2") (pinfunction "DO(IO1)_2") (pintype "bidirectional"))
      (node (ref "U2") (pin "27") (pinfunction "IO2_27") (pintype "bidirectional"))
    )
    (net (code "20") (name "MOSI") (class "Default")
      (node (ref "D11") (pin "2") (pinfunction "2_2") (pintype "passive"))
      (node (ref "J1") (pin "14") (pinfunction "14_14") (pintype "bidirectional"))
      (node (ref "J4") (pin "P3") (pinfunction "CMD_P3") (pintype "bidirectional"))
      (node (ref "R7") (pin "1") (pinfunction "1_1") (pintype "passive"))
      (node (ref "TP7") (pin "TP") (pinfunction "TP_TP") (pintype "input"))
      (node (ref "U1") (pin "5") (pinfunction "DI(IO0)_5") (pintype "bidirectional"))
      (node (ref "U2") (pin "7") (pinfunction "IO7_7") (pintype "bidirectional"))
    )
    (net (code "21") (name "Net-(CHG_LED-PadC)") (class "Default")
      (node (ref "CHG_LED") (pin "C") (pinfunction "C_C") (pintype "passive"))
      (node (ref "R1_BAT") (pin "1") (pinfunction "1_1") (pintype "passive"))
    )
    (net (code "22") (name "Net-(D2-CATHODE)") (class "Default")
      (node (ref "C1_BAT1") (pin "1") (pinfunction "1_1") (pintype "passive"))
      (node (ref "D2") (pin "1") (pinfunction "CATHODE_1") (pintype "bidirectional"))
      (node (ref "IC4") (pin "1") (pinfunction "VIN_1") (pintype "bidirectional"))
      (node (ref "IC4") (pin "3") (pinfunction "CE_3") (pintype "bidirectional"))
      (node (ref "Q1") (pin "2") (pinfunction "S_2") (pintype "bidirectional"))
    )
    (net (code "23") (name "Net-(D3-A)") (class "Default")
      (node (ref "C4") (pin "1") (pinfunction "1_1") (pintype "passive"))
      (node (ref "D3") (pin "2") (pinfunction "A_2") (pintype "bidirectional"))
      (node (ref "D4") (pin "1") (pinfunction "K_1") (pintype "bidirectional"))
    )
    (net (code "24") (name "Net-(D7-CATHODE)") (class "Default")
      (node (ref "D7") (pin "1") (pinfunction "CATHODE_1") (pintype "bidirectional"))
      (node (ref "R_CAPACITOR") (pin "2") (pinfunction "2_2") (pintype "passive"))
    )
    (net (code "25") (name "Net-(EPD_C1-Pad1)") (class "Default")
      (node (ref "EPD_C1") (pin "1") (pinfunction "1_1") (pintype "passive"))
      (node (ref "J1") (pin "4") (pinfunction "4_4") (pintype "bidirectional"))
    )
    (net (code "26") (name "Net-(EPD_C2-Pad1)") (class "Default")
      (node (ref "EPD_C2") (pin "1") (pinfunction "1_1") (pintype "passive"))
      (node (ref "J1") (pin "5") (pinfunction "5_5") (pintype "bidirectional"))
    )
    (net (code "27") (name "Net-(EPD_C6-Pad1)") (class "Default")
      (node (ref "EPD_C6") (pin "1") (pinfunction "1_1") (pintype "passive"))
      (node (ref "J1") (pin "18") (pinfunction "18_18") (pintype "bidirectional"))
    )
    (net (code "28") (name "Net-(EPD_C7-Pad1)") (class "Default")
      (node (ref "EPD_C7") (pin "1") (pinfunction "1_1") (pintype "passive"))
      (node (ref "J1") (pin "19") (pinfunction "19_19") (pintype "bidirectional"))
    )
    (net (code "29") (name "Net-(EPD_C8-Pad1)") (class "Default")
      (node (ref "EPD_C8") (pin "1") (pinfunction "1_1") (pintype "passive"))
      (node (ref "J1") (pin "20") (pinfunction "20_20") (pintype "bidirectional"))
    )
    (net (code "30") (name "Net-(EPD_C10-Pad1)") (class "Default")
      (node (ref "EPD_C10") (pin "1") (pinfunction "1_1") (pintype "passive"))
      (node (ref "J1") (pin "22") (pinfunction "22_22") (pintype "bidirectional"))
    )
    (net (code "31") (name "Net-(EPD_C12-Pad1)") (class "Default")
      (node (ref "EPD_C12") (pin "1") (pinfunction "1_1") (pintype "passive"))
      (node (ref "J1") (pin "24") (pinfunction "24_24") (pintype "bidirectional"))
    )
    (net (code "32") (name "Net-(IC1-CT)") (class "Default")
      (node (ref "C_DELAY") (pin "1") (pinfunction "1_1") (pintype "passive"))
      (node (ref "IC1") (pin "5") (pinfunction "CT_5") (pintype "bidirectional"))
    )
    (net (code "33") (name "Net-(J2-PadA5)") (class "Default")
      (node (ref "J2") (pin "A5") (pinfunction "A5_A5") (pintype "bidirectional"))
      (node (ref "R2-USB1") (pin "2") (pinfunction "2_2") (pintype "passive"))
    )
    (net (code "34") (name "Net-(J2-PadB5)") (class "Default")
      (node (ref "J2") (pin "B5") (pinfunction "B5_B5") (pintype "bidirectional"))
      (node (ref "R2-USB2") (pin "1") (pinfunction "1_1") (pintype "passive"))
    )
    (net (code "35") (name "Net-(MCP73831-PROG)") (class "Default")
      (node (ref "MCP73831") (pin "5") (pinfunction "PROG_5") (pintype "input"))
      (node (ref "R2_BAT") (pin "2") (pinfunction "2_2") (pintype "passive"))
    )
    (net (code "36") (name "Net-(MCP73831-STAT)") (class "Default")
      (node (ref "MCP73831") (pin "1") (pinfunction "STAT_1") (pintype "output"))
      (node (ref "R1_BAT") (pin "2") (pinfunction "2_2") (pintype "passive"))
    )
    (net (code "37") (name "PREVGH") (class "Default")
      (node (ref "D5") (pin "1") (pinfunction "K_1") (pintype "bidirectional"))
      (node (ref "EPD_C9") (pin "1") (pinfunction "1_1") (pintype "passive"))
      (node (ref "J1") (pin "21") (pinfunction "21_21") (pintype "bidirectional"))
    )
    (net (code "38") (name "PREVGL") (class "Default")
      (node (ref "D4") (pin "2") (pinfunction "A_2") (pintype "bidirectional"))
      (node (ref "EPD_C11") (pin "1") (pinfunction "1_1") (pintype "passive"))
      (node (ref "J1") (pin "23") (pinfunction "23_23") (pintype "bidirectional"))
    )
    (net (code "39") (name "RESE") (class "Default")
      (node (ref "J1") (pin "3") (pinfunction "3_3") (pintype "bidirectional"))
      (node (ref "Q3") (pin "2") (pinfunction "S_2") (pintype "bidirectional"))
      (node (ref "R3") (pin "2") (pinfunction "2_2") (pintype "passive"))
    )
    (net (code "40") (name "RESE'") (class "Default")
      (node (ref "R2") (pin "2") (pinfunction "2_2") (pintype "passive"))
      (node (ref "R3") (pin "1") (pinfunction "1_1") (pintype "passive"))
      (node (ref "SJ1") (pin "2") (pinfunction "2_2") (pintype "passive"))
    )
    (net (code "41") (name "RESET") (class "Default")
      (node (ref "C5") (pin "1") (pinfunction "1_1") (pintype "passive"))
      (node (ref "IC1") (pin "1") (pinfunction "VOUT_1") (pintype "bidirectional"))
      (node (ref "RESET_BUTTON") (pin "3") (pinfunction "3_3") (pintype "passive"))
      (node (ref "RESET_BUTTON") (pin "4") (pinfunction "4_4") (pintype "passive"))
      (node (ref "R_RESET") (pin "1") (pinfunction "1_1") (pintype "passive"))
      (node (ref "U2") (pin "3") (pinfunction "EN_3") (pintype "input"))
    )
    (net (code "42") (name "RTC_RST") (class "Default")
      (node (ref "U2") (pin "16") (pinfunction "IO18_16") (pintype "bidirectional"))
      (node (ref "U3") (pin "4") (pinfunction "~{RST}_4") (pintype "input"))
    )
    (net (code "43") (name "RX") (class "Default")
      (node (ref "TP2") (pin "TP") (pinfunction "TP_TP") (pintype "input"))
      (node (ref "U2") (pin "24") (pinfunction "RXD0/GPIO17_24") (pintype "bidirectional"))
    )
    (net (code "44") (name "SCK") (class "Default")
      (node (ref "D10") (pin "2") (pinfunction "2_2") (pintype "passive"))
      (node (ref "J1") (pin "13") (pinfunction "13_13") (pintype "bidirectional"))
      (node (ref "J4") (pin "P5") (pinfunction "CLK_P5") (pintype "bidirectional"))
      (node (ref "R6") (pin "1") (pinfunction "1_1") (pintype "passive"))
      (node (ref "TP8") (pin "TP") (pinfunction "TP_TP") (pintype "input"))
      (node (ref "U1") (pin "6") (pinfunction "CLK_6") (pintype "input"))
      (node (ref "U2") (pin "6") (pinfunction "IO6_6") (pintype "bidirectional"))
    )
    (net (code "45") (name "SCL") (class "Default")
      (node (ref "J3") (pin "4") (pinfunction "4_4") (pintype "passive"))
      (node (ref "R2-PINH") (pin "1") (pinfunction "1_1") (pintype "passive"))
      (node (ref "SENSOR2") (pin "4") (pinfunction "SCK_4") (pintype "input"))
      (node (ref "U2") (pin "20") (pinfunction "IO22_20") (pintype "bidirectional"))
      (node (ref "U3") (pin "16") (pinfunction "SCL_16") (pintype "input"))
      (node (ref "U4") (pin "7") (pinfunction "SCL_7") (pintype "input"))
    )
    (net (code "46") (name "SDA") (class "Default")
      (node (ref "J3") (pin "3") (pinfunction "3_3") (pintype "passive"))
      (node (ref "R1_PINH") (pin "1") (pinfunction "1_1") (pintype "passive"))
      (node (ref "SENSOR2") (pin "3") (pinfunction "SDI_3") (pintype "bidirectional"))
      (node (ref "U2") (pin "19") (pinfunction "IO21_19") (pintype "bidirectional"))
      (node (ref "U3") (pin "15") (pinfunction "SDA_15") (pintype "bidirectional"))
      (node (ref "U4") (pin "8") (pinfunction "SDA_8") (pintype "bidirectional"))
    )
    (net (code "47") (name "SRC") (class "Default")
      (node (ref "C4") (pin "2") (pinfunction "2_2") (pintype "passive"))
      (node (ref "D5") (pin "2") (pinfunction "A_2") (pintype "bidirectional"))
      (node (ref "L1") (pin "1") (pinfunction "1_1") (pintype "passive"))
      (node (ref "Q3") (pin "3") (pinfunction "D_3") (pintype "bidirectional"))
    )
    (net (code "48") (name "SS_SD") (class "Default")
      (node (ref "D8") (pin "2") (pinfunction "2_2") (pintype "passive"))
      (node (ref "J4") (pin "P2") (pinfunction "CD/DAT3_P2") (pintype "bidirectional"))
      (node (ref "R10") (pin "1") (pinfunction "1_1") (pintype "passive"))
      (node (ref "U2") (pin "4") (pinfunction "IO4_4") (pintype "bidirectional"))
    )
    (net (code "49") (name "TX") (class "Default")
      (node (ref "TP1") (pin "TP") (pinfunction "TP_TP") (pintype "input"))
      (node (ref "U2") (pin "25") (pinfunction "TXD0/GPIO16_25") (pintype "bidirectional"))
    )
    (net (code "50") (name "USB_D+") (class "Default")
      (node (ref "D1") (pin "1") (pinfunction "I/O1_1_1") (pintype "bidirectional"))
      (node (ref "U2") (pin "14") (pinfunction "IO13_14") (pintype "bidirectional"))
    )
    (net (code "51") (name "USB_D-") (class "Default")
      (node (ref "D1") (pin "3") (pinfunction "I/O2_1_3") (pintype "bidirectional"))
      (node (ref "U2") (pin "13") (pinfunction "IO12_13") (pintype "bidirectional"))
    )
    (net (code "52") (name "VBAT") (class "Default")
      (node (ref "C2_BAT") (pin "1") (pinfunction "1_1") (pintype "passive"))
      (node (ref "MCP73831") (pin "3") (pinfunction "VBAT_3") (pintype "power_in"))
      (node (ref "Q1") (pin "3") (pinfunction "D_3") (pintype "bidirectional"))
      (node (ref "TP3") (pin "TP") (pinfunction "TP_TP") (pintype "input"))
      (node (ref "U4") (pin "2") (pinfunction "CELL_2") (pintype "power_in"))
      (node (ref "U4") (pin "3") (pinfunction "VDD_3") (pintype "power_in"))
    )
    (net (code "53") (name "VBUS") (class "Default")
      (node (ref "C1_BAT") (pin "1") (pinfunction "1_1") (pintype "passive"))
      (node (ref "C4_USB") (pin "1") (pinfunction "1_1") (pintype "passive"))
      (node (ref "C5_USB") (pin "1") (pinfunction "1_1") (pintype "passive"))
      (node (ref "CHG_LED") (pin "A") (pinfunction "A_A") (pintype "passive"))
      (node (ref "D1") (pin "5") (pinfunction "VBUS_5") (pintype "bidirectional"))
      (node (ref "D2") (pin "2") (pinfunction "ANODE_2") (pintype "bidirectional"))
      (node (ref "MCP73831") (pin "4") (pinfunction "VIN_4") (pintype "power_in"))
      (node (ref "PFMF.050.1") (pin "2") (pinfunction "2_2") (pintype "passive"))
      (node (ref "Q1") (pin "1") (pinfunction "G_1") (pintype "bidirectional"))
      (node (ref "R1_PWRUSB") (pin "2") (pinfunction "2_2") (pintype "passive"))
      (node (ref "TP14") (pin "TP") (pinfunction "TP_TP") (pintype "input"))
    )
    (net (code "54") (name "VRTC") (class "Default")
      (node (ref "C10_SUPERCAP") (pin "2") (pinfunction "2_2") (pintype "passive"))
      (node (ref "C8") (pin "1") (pinfunction "1_1") (pintype "passive"))
      (node (ref "R_CAPACITOR") (pin "1") (pinfunction "1_1") (pintype "passive"))
      (node (ref "U3") (pin "14") (pinfunction "VBAT_14") (pintype "power_in"))
    )
    (net (code "55") (name "VUSB") (class "Default")
      (node (ref "J2") (pin "A4") (pinfunction "A4_A4") (pintype "bidirectional"))
      (node (ref "J2") (pin "A9") (pinfunction "A9_A9") (pintype "bidirectional"))
      (node (ref "J2") (pin "B4") (pinfunction "B4_B4") (pintype "bidirectional"))
      (node (ref "J2") (pin "B9") (pinfunction "B9_B9") (pintype "bidirectional"))
      (node (ref "PFMF.050.1") (pin "1") (pinfunction "1_1") (pintype "passive"))
    )
    (net (code "56") (name "unconnected-(IC1-NC-Pad4)") (class "Default")
      (node (ref "IC1") (pin "4") (pinfunction "NC_4") (pintype "no_connect"))
    )
    (net (code "57") (name "unconnected-(IC4-NC-Pad4)") (class "Default")
      (node (ref "IC4") (pin "4") (pinfunction "NC_4") (pintype "no_connect"))
    )
    (net (code "58") (name "unconnected-(J1-Pad1)") (class "Default")
      (node (ref "J1") (pin "1") (pinfunction "1_1") (pintype "bidirectional"))
    )
    (net (code "59") (name "unconnected-(J1-Pad6)") (class "Default")
      (node (ref "J1") (pin "6") (pinfunction "6_6") (pintype "bidirectional"))
    )
    (net (code "60") (name "unconnected-(J1-Pad7)") (class "Default")
      (node (ref "J1") (pin "7") (pinfunction "7_7") (pintype "bidirectional"))
    )
    (net (code "61") (name "unconnected-(J2-PadA8)") (class "Default")
      (node (ref "J2") (pin "A8") (pinfunction "A8_A8") (pintype "bidirectional"))
    )
    (net (code "62") (name "unconnected-(J2-PadB8)") (class "Default")
      (node (ref "J2") (pin "B8") (pinfunction "B8_B8") (pintype "bidirectional"))
    )
    (net (code "63") (name "unconnected-(J4-DAT1-PadP8)") (class "Default")
      (node (ref "J4") (pin "P8") (pinfunction "DAT1_P8") (pintype "bidirectional"))
    )
    (net (code "64") (name "unconnected-(J4-DAT2-PadP1)") (class "Default")
      (node (ref "J4") (pin "P1") (pinfunction "DAT2_P1") (pintype "bidirectional"))
    )
    (net (code "65") (name "unconnected-(J4-DETECTION_1-PadS1)") (class "Default")
      (node (ref "J4") (pin "S1") (pinfunction "DETECTION_1_S1") (pintype "bidirectional"))
    )
    (net (code "66") (name "unconnected-(J4-DETECTION_2-PadS2)") (class "Default")
      (node (ref "J4") (pin "S2") (pinfunction "DETECTION_2_S2") (pintype "bidirectional"))
    )
    (net (code "67") (name "unconnected-(U2-NC-Pad22)") (class "Default")
      (node (ref "U2") (pin "22") (pinfunction "NC_22") (pintype "no_connect"))
    )
    (net (code "68") (name "unconnected-(U4-~{ALERT}-Pad5)") (class "Default")
      (node (ref "U4") (pin "5") (pinfunction "~{ALERT}_5") (pintype "output"))
    )
  )
)
